# WLB_DOC.net
KiCad netlist of a schematic drawn in Altium Designer
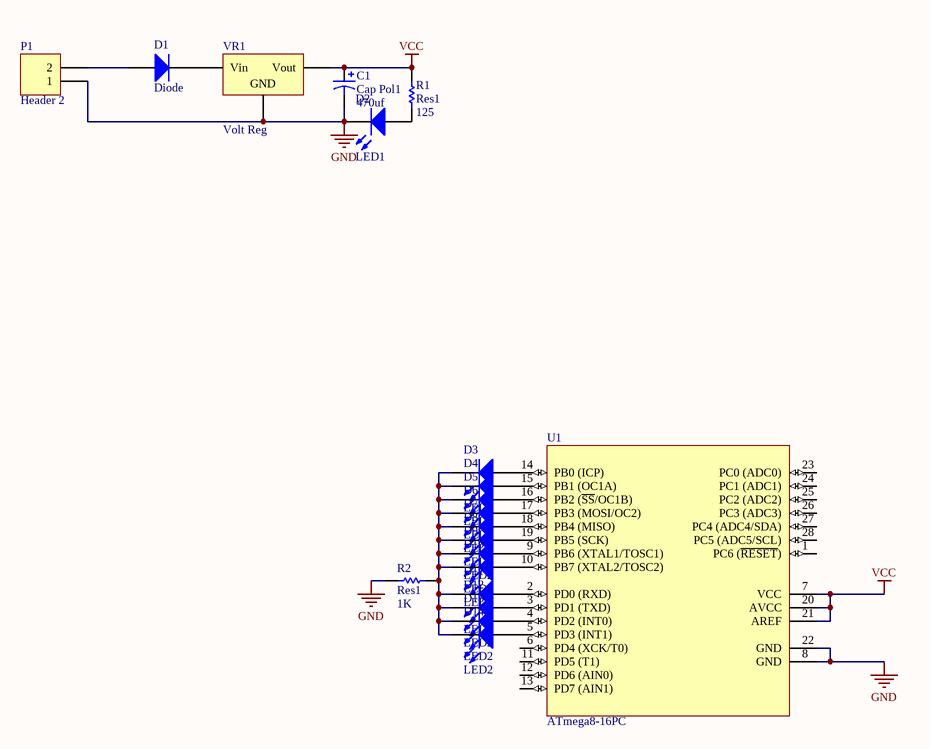
[diagram p0: WLB_DOC.SchDoc]

(export (version "E")
  (design (tool "Eeschema 10.0.6"))
  (components
    (comp (ref "C1")
      (value "Cap Pol1")
      (footprint "RB7.6-15")
      (description "Polarized Capacitor (Radial)")
      (fields (field (name "ALTIUM_VALUE") "470uf") (field (name "PUBLISHER") "Altium Limited"))
      (libsource (lib "Miscellaneous Devices") (part "Cap Pol1"))
    )
    (comp (ref "D1")
      (value "Diode")
      (footprint "SMC")
      (description "Default Diode")
      (fields (field (name "PUBLISHER") "Altium Limited"))
      (libsource (lib "Miscellaneous Devices") (part "Diode"))
    )
    (comp (ref "D2")
      (value "LED1")
      (footprint "LED-1")
      (description "Typical RED GaAs LED")
      (fields (field (name "PUBLISHER") "Altium Limited"))
      (libsource (lib "Miscellaneous Devices") (part "LED1"))
    )
    (comp (ref "D3")
      (value "LED2")
      (footprint "3.2X1.6X1.1")
      (description "Typical RED, GREEN, YELLOW, AMBER GaAs LED")
      (fields (field (name "PUBLISHER") "Altium Limited"))
      (libsource (lib "Miscellaneous Devices") (part "LED2"))
    )
    (comp (ref "D4")
      (value "LED2")
      (footprint "3.2X1.6X1.1")
      (description "Typical RED, GREEN, YELLOW, AMBER GaAs LED")
      (fields (field (name "PUBLISHER") "Altium Limited"))
      (libsource (lib "Miscellaneous Devices") (part "LED2"))
    )
    (comp (ref "D5")
      (value "LED2")
      (footprint "3.2X1.6X1.1")
      (description "Typical RED, GREEN, YELLOW, AMBER GaAs LED")
      (fields (field (name "PUBLISHER") "Altium Limited"))
      (libsource (lib "Miscellaneous Devices") (part "LED2"))
    )
    (comp (ref "D6")
      (value "LED2")
      (footprint "3.2X1.6X1.1")
      (description "Typical RED, GREEN, YELLOW, AMBER GaAs LED")
      (fields (field (name "PUBLISHER") "Altium Limited"))
      (libsource (lib "Miscellaneous Devices") (part "LED2"))
    )
    (comp (ref "D7")
      (value "LED2")
      (footprint "3.2X1.6X1.1")
      (description "Typical RED, GREEN, YELLOW, AMBER GaAs LED")
      (fields (field (name "PUBLISHER") "Altium Limited"))
      (libsource (lib "Miscellaneous Devices") (part "LED2"))
    )
    (comp (ref "D8")
      (value "LED2")
      (footprint "3.2X1.6X1.1")
      (description "Typical RED, GREEN, YELLOW, AMBER GaAs LED")
      (fields (field (name "PUBLISHER") "Altium Limited"))
      (libsource (lib "Miscellaneous Devices") (part "LED2"))
    )
    (comp (ref "D9")
      (value "LED2")
      (footprint "3.2X1.6X1.1")
      (description "Typical RED, GREEN, YELLOW, AMBER GaAs LED")
      (fields (field (name "PUBLISHER") "Altium Limited"))
      (libsource (lib "Miscellaneous Devices") (part "LED2"))
    )
    (comp (ref "D10")
      (value "LED2")
      (footprint "3.2X1.6X1.1")
      (description "Typical RED, GREEN, YELLOW, AMBER GaAs LED")
      (fields (field (name "PUBLISHER") "Altium Limited"))
      (libsource (lib "Miscellaneous Devices") (part "LED2"))
    )
    (comp (ref "D11")
      (value "LED2")
      (footprint "3.2X1.6X1.1")
      (description "Typical RED, GREEN, YELLOW, AMBER GaAs LED")
      (fields (field (name "PUBLISHER") "Altium Limited"))
      (libsource (lib "Miscellaneous Devices") (part "LED2"))
    )
    (comp (ref "D12")
      (value "LED2")
      (footprint "3.2X1.6X1.1")
      (description "Typical RED, GREEN, YELLOW, AMBER GaAs LED")
      (fields (field (name "PUBLISHER") "Altium Limited"))
      (libsource (lib "Miscellaneous Devices") (part "LED2"))
    )
    (comp (ref "D13")
      (value "LED2")
      (footprint "3.2X1.6X1.1")
      (description "Typical RED, GREEN, YELLOW, AMBER GaAs LED")
      (fields (field (name "PUBLISHER") "Altium Limited"))
      (libsource (lib "Miscellaneous Devices") (part "LED2"))
    )
    (comp (ref "D14")
      (value "LED2")
      (footprint "3.2X1.6X1.1")
      (description "Typical RED, GREEN, YELLOW, AMBER GaAs LED")
      (fields (field (name "PUBLISHER") "Altium Limited"))
      (libsource (lib "Miscellaneous Devices") (part "LED2"))
    )
    (comp (ref "P1")
      (value "Header 2")
      (footprint "HDR1X2")
      (description "Header, 2-Pin")
      (fields (field (name "PUBLISHER") "Altium Limited"))
      (libsource (lib "Miscellaneous Connectors") (part "Header 2"))
    )
    (comp (ref "R1")
      (value "Res1")
      (footprint "AXIAL-0.3")
      (description "Resistor")
      (fields (field (name "ALTIUM_VALUE") "125") (field (name "PUBLISHER") "Altium Limited"))
      (libsource (lib "Miscellaneous Devices") (part "Res1"))
    )
    (comp (ref "R2")
      (value "Res1")
      (footprint "AXIAL-0.3")
      (description "Resistor")
      (fields (field (name "ALTIUM_VALUE") "1K") (field (name "PUBLISHER") "Altium Limited"))
      (libsource (lib "Miscellaneous Devices") (part "Res1"))
    )
    (comp (ref "U1")
      (value "ATmega8-16PC")
      (footprint "28P3")
      (description "8-Bit AVR Microcontroller with 8K Bytes of In-System Programmable Flash Memory")
      (fields (field (name "PUBLISHER") "Altium Limited"))
      (libsource (lib "Atmel Microcontroller 8-Bit AVR") (part "ATmega8-16PC"))
    )
    (comp (ref "VR1")
      (value "Volt Reg")
      (footprint "D2PAK_N")
      (description "Voltage Regulator")
      (fields (field (name "PUBLISHER") "Altium Limited"))
      (libsource (lib "Miscellaneous Devices") (part "Volt Reg"))
    )
  )
  (nets
    (net (code "1") (name "GND") (class "Default")
      (node (ref "C1") (pin "2") (pinfunction "2_2") (pintype "passive"))
      (node (ref "D2") (pin "2") (pinfunction "K_2") (pintype "passive"))
      (node (ref "P1") (pin "1") (pinfunction "1_1") (pintype "passive"))
      (node (ref "R2") (pin "1") (pinfunction "1_1") (pintype "passive"))
      (node (ref "U1") (pin "22") (pinfunction "GND_22") (pintype "power_in"))
      (node (ref "U1") (pin "8") (pinfunction "GND_8") (pintype "power_in"))
      (node (ref "VR1") (pin "2") (pinfunction "GND_2") (pintype "passive"))
    )
    (net (code "2") (name "Net-(D1-A)") (class "Default")
      (node (ref "D1") (pin "1") (pinfunction "A_1") (pintype "passive"))
      (node (ref "P1") (pin "2") (pinfunction "2_2") (pintype "passive"))
    )
    (net (code "3") (name "Net-(D1-K)") (class "Default")
      (node (ref "D1") (pin "2") (pinfunction "K_2") (pintype "passive"))
      (node (ref "VR1") (pin "1") (pinfunction "Vin_1") (pintype "passive"))
    )
    (net (code "4") (name "Net-(D2-A)") (class "Default")
      (node (ref "D2") (pin "1") (pinfunction "A_1") (pintype "passive"))
      (node (ref "R1") (pin "1") (pinfunction "1_1") (pintype "passive"))
    )
    (net (code "5") (name "Net-(D3-A)") (class "Default")
      (node (ref "D3") (pin "1") (pinfunction "A_1") (pintype "passive"))
      (node (ref "U1") (pin "14") (pinfunction "PB0_(ICP)_14") (pintype "bidirectional"))
    )
    (net (code "6") (name "Net-(D4-A)") (class "Default")
      (node (ref "D4") (pin "1") (pinfunction "A_1") (pintype "passive"))
      (node (ref "U1") (pin "15") (pinfunction "PB1_(OC1A)_15") (pintype "bidirectional"))
    )
    (net (code "7") (name "Net-(D5-A)") (class "Default")
      (node (ref "D5") (pin "1") (pinfunction "A_1") (pintype "passive"))
      (node (ref "U1") (pin "16") (pinfunction "PB2_(~{SS}/OC1B)_16") (pintype "bidirectional"))
    )
    (net (code "8") (name "Net-(D6-A)") (class "Default")
      (node (ref "D6") (pin "1") (pinfunction "A_1") (pintype "passive"))
      (node (ref "U1") (pin "17") (pinfunction "PB3_(MOSI/OC2)_17") (pintype "bidirectional"))
    )
    (net (code "9") (name "Net-(D7-A)") (class "Default")
      (node (ref "D7") (pin "1") (pinfunction "A_1") (pintype "passive"))
      (node (ref "U1") (pin "18") (pinfunction "PB4_(MISO)_18") (pintype "bidirectional"))
    )
    (net (code "10") (name "Net-(D8-A)") (class "Default")
      (node (ref "D8") (pin "1") (pinfunction "A_1") (pintype "passive"))
      (node (ref "U1") (pin "19") (pinfunction "PB5_(SCK)_19") (pintype "bidirectional"))
    )
    (net (code "11") (name "Net-(D9-A)") (class "Default")
      (node (ref "D9") (pin "1") (pinfunction "A_1") (pintype "passive"))
      (node (ref "U1") (pin "9") (pinfunction "PB6_(XTAL1/TOSC1)_9") (pintype "bidirectional"))
    )
    (net (code "12") (name "Net-(D10-A)") (class "Default")
      (node (ref "D10") (pin "1") (pinfunction "A_1") (pintype "passive"))
      (node (ref "U1") (pin "10") (pinfunction "PB7_(XTAL2/TOSC2)_10") (pintype "bidirectional"))
    )
    (net (code "13") (name "Net-(D10-K)") (class "Default")
      (node (ref "D10") (pin "2") (pinfunction "K_2") (pintype "passive"))
      (node (ref "D11") (pin "2") (pinfunction "K_2") (pintype "passive"))
      (node (ref "D12") (pin "2") (pinfunction "K_2") (pintype "passive"))
      (node (ref "D13") (pin "2") (pinfunction "K_2") (pintype "passive"))
      (node (ref "D14") (pin "2") (pinfunction "K_2") (pintype "passive"))
      (node (ref "D3") (pin "2") (pinfunction "K_2") (pintype "passive"))
      (node (ref "D4") (pin "2") (pinfunction "K_2") (pintype "passive"))
      (node (ref "D5") (pin "2") (pinfunction "K_2") (pintype "passive"))
      (node (ref "D6") (pin "2") (pinfunction "K_2") (pintype "passive"))
      (node (ref "D7") (pin "2") (pinfunction "K_2") (pintype "passive"))
      (node (ref "D8") (pin "2") (pinfunction "K_2") (pintype "passive"))
      (node (ref "D9") (pin "2") (pinfunction "K_2") (pintype "passive"))
      (node (ref "R2") (pin "2") (pinfunction "2_2") (pintype "passive"))
    )
    (net (code "14") (name "Net-(D11-A)") (class "Default")
      (node (ref "D11") (pin "1") (pinfunction "A_1") (pintype "passive"))
      (node (ref "U1") (pin "2") (pinfunction "PD0_(RXD)_2") (pintype "bidirectional"))
    )
    (net (code "15") (name "Net-(D12-A)") (class "Default")
      (node (ref "D12") (pin "1") (pinfunction "A_1") (pintype "passive"))
      (node (ref "U1") (pin "3") (pinfunction "PD1_(TXD)_3") (pintype "bidirectional"))
    )
    (net (code "16") (name "Net-(D13-A)") (class "Default")
      (node (ref "D13") (pin "1") (pinfunction "A_1") (pintype "passive"))
      (node (ref "U1") (pin "4") (pinfunction "PD2_(INT0)_4") (pintype "bidirectional"))
    )
    (net (code "17") (name "Net-(D14-A)") (class "Default")
      (node (ref "D14") (pin "1") (pinfunction "A_1") (pintype "passive"))
      (node (ref "U1") (pin "5") (pinfunction "PD3_(INT1)_5") (pintype "bidirectional"))
    )
    (net (code "18") (name "VCC") (class "Default")
      (node (ref "C1") (pin "1") (pinfunction "1_1") (pintype "passive"))
      (node (ref "R1") (pin "2") (pinfunction "2_2") (pintype "passive"))
      (node (ref "U1") (pin "20") (pinfunction "AVCC_20") (pintype "power_in"))
      (node (ref "U1") (pin "21") (pinfunction "AREF_21") (pintype "passive"))
      (node (ref "U1") (pin "7") (pinfunction "VCC_7") (pintype "power_in"))
      (node (ref "VR1") (pin "3") (pinfunction "Vout_3") (pintype "passive"))
    )
    (net (code "19") (name "unconnected-(U1-PC0_(ADC0)-Pad23)") (class "Default")
      (node (ref "U1") (pin "23") (pinfunction "PC0_(ADC0)_23") (pintype "bidirectional"))
    )
    (net (code "20") (name "unconnected-(U1-PC1_(ADC1)-Pad24)") (class "Default")
      (node (ref "U1") (pin "24") (pinfunction "PC1_(ADC1)_24") (pintype "bidirectional"))
    )
    (net (code "21") (name "unconnected-(U1-PC2_(ADC2)-Pad25)") (class "Default")
      (node (ref "U1") (pin "25") (pinfunction "PC2_(ADC2)_25") (pintype "bidirectional"))
    )
    (net (code "22") (name "unconnected-(U1-PC3_(ADC3)-Pad26)") (class "Default")
      (node (ref "U1") (pin "26") (pinfunction "PC3_(ADC3)_26") (pintype "bidirectional"))
    )
    (net (code "23") (name "unconnected-(U1-PC4_(ADC4{slash}SDA)-Pad27)") (class "Default")
      (node (ref "U1") (pin "27") (pinfunction "PC4_(ADC4/SDA)_27") (pintype "bidirectional"))
    )
    (net (code "24") (name "unconnected-(U1-PC5_(ADC5{slash}SCL)-Pad28)") (class "Default")
      (node (ref "U1") (pin "28") (pinfunction "PC5_(ADC5/SCL)_28") (pintype "bidirectional"))
    )
    (net (code "25") (name "unconnected-(U1-PC6_(~{RESET})-Pad1)") (class "Default")
      (node (ref "U1") (pin "1") (pinfunction "PC6_(~{RESET})_1") (pintype "bidirectional"))
    )
    (net (code "26") (name "unconnected-(U1-PD4_(XCK{slash}T0)-Pad6)") (class "Default")
      (node (ref "U1") (pin "6") (pinfunction "PD4_(XCK/T0)_6") (pintype "bidirectional"))
    )
    (net (code "27") (name "unconnected-(U1-PD5_(T1)-Pad11)") (class "Default")
      (node (ref "U1") (pin "11") (pinfunction "PD5_(T1)_11") (pintype "bidirectional"))
    )
    (net (code "28") (name "unconnected-(U1-PD6_(AIN0)-Pad12)") (class "Default")
      (node (ref "U1") (pin "12") (pinfunction "PD6_(AIN0)_12") (pintype "bidirectional"))
    )
    (net (code "29") (name "unconnected-(U1-PD7_(AIN1)-Pad13)") (class "Default")
      (node (ref "U1") (pin "13") (pinfunction "PD7_(AIN1)_13") (pintype "bidirectional"))
    )
  )
)
